# MegaSineShield.net
KiCad netlist of a schematic drawn in EAGLE
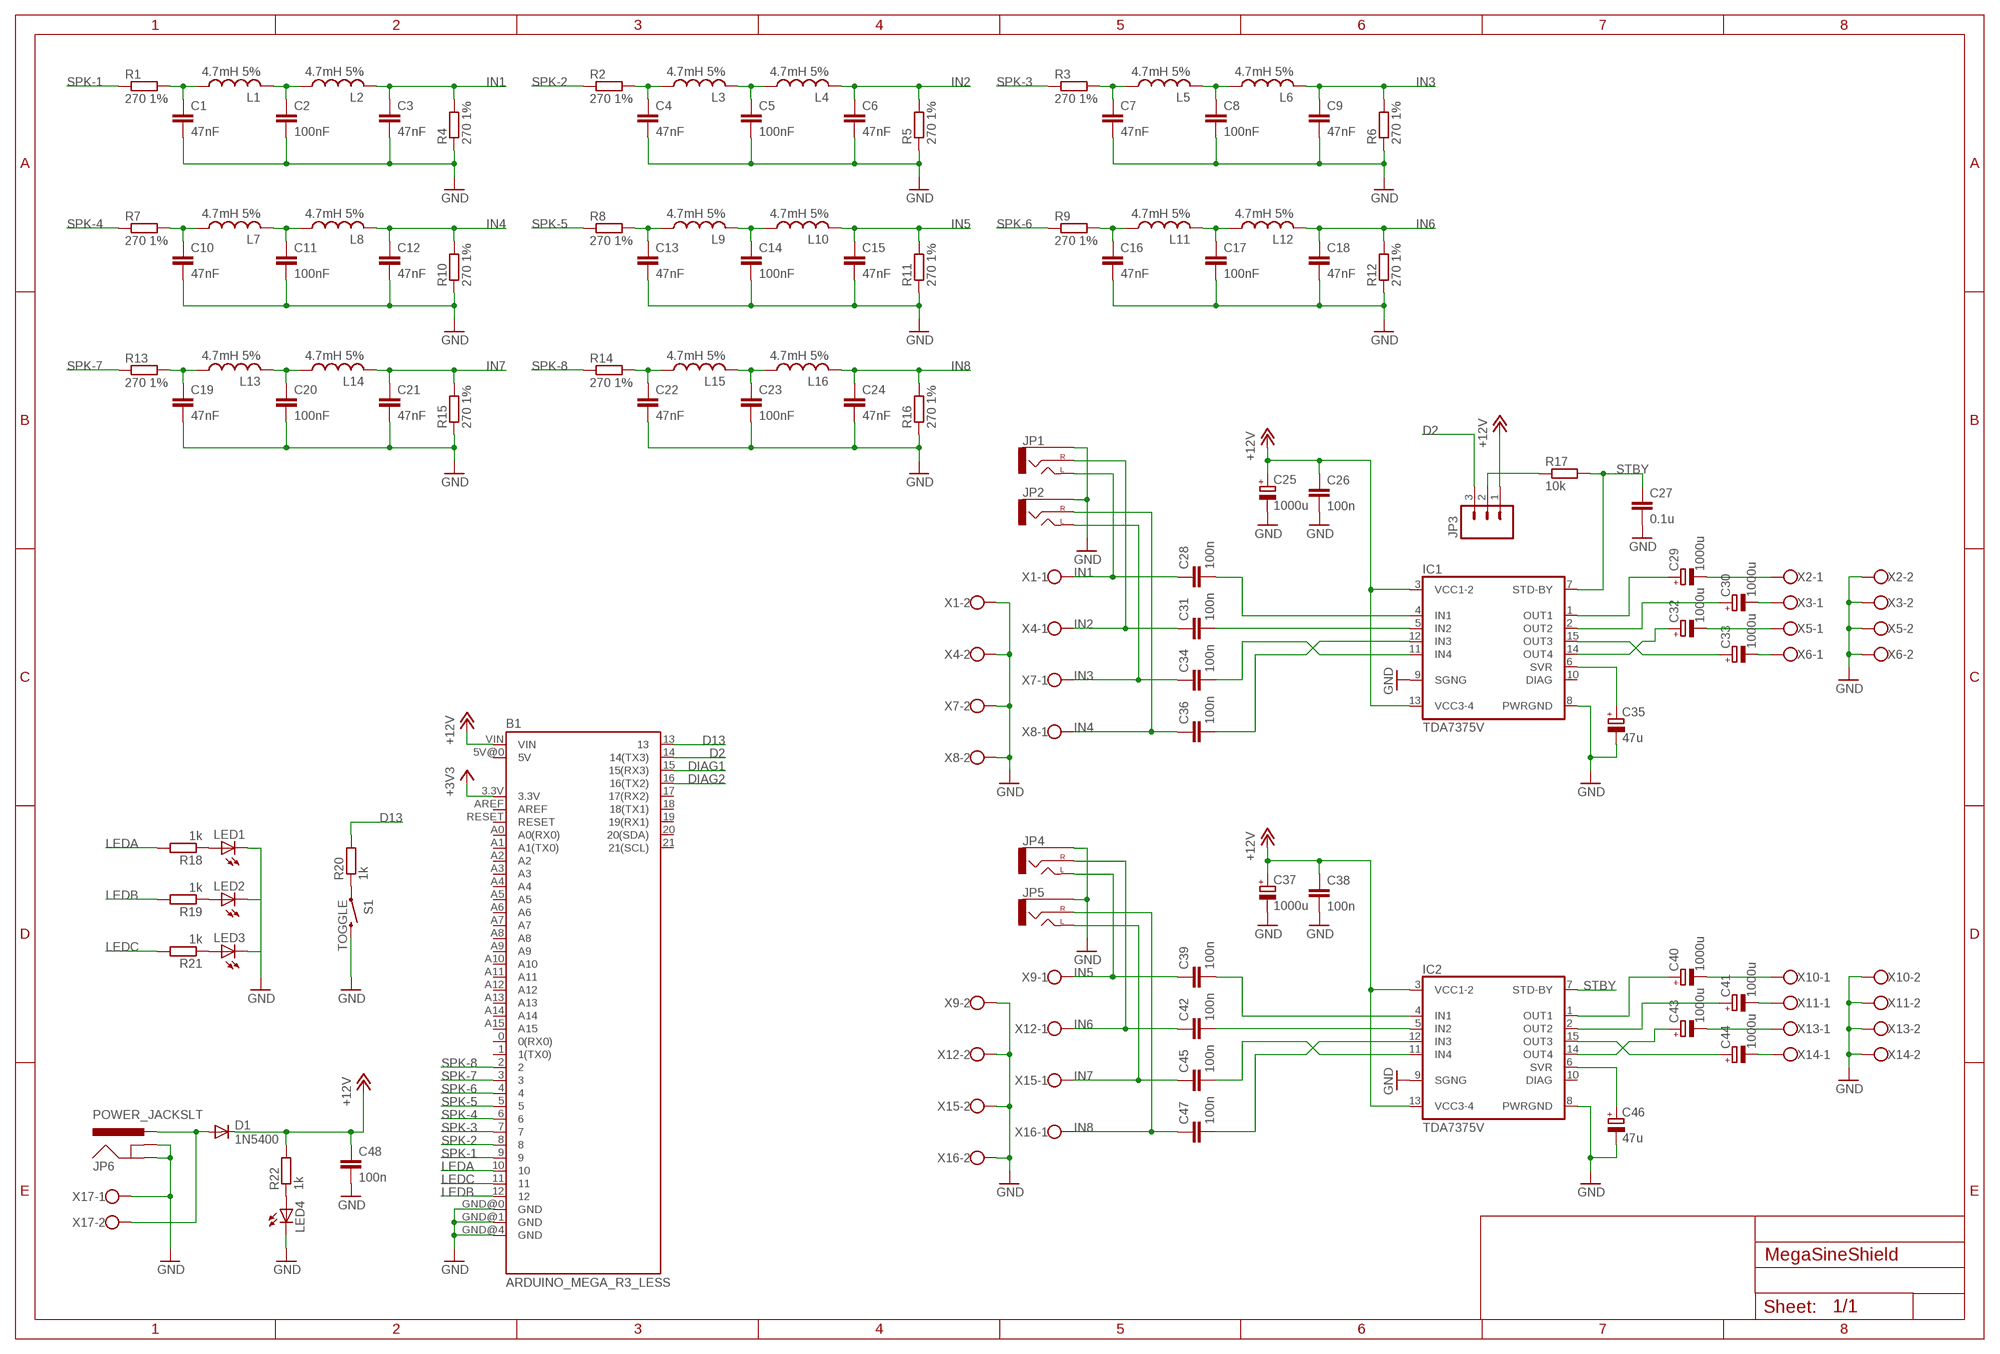
[diagram p0: schematic, sheet 1]

(export (version "E")
  (design (tool "Eeschema 10.0.6"))
  (components
    (comp (ref "B1")
      (value "ARDUINO_MEGA_R3_LESS")
      (footprint "eagle-import:ARDUINO_MEGA_LESS")
      (libsource (lib "eagle-import") (part "ARDUINO_MEGA_R3_LESS"))
    )
    (comp (ref "C1")
      (value "47nF")
      (footprint "eagle-import:C025-025X050")
      (libsource (lib "eagle-import") (part "C-EU025-025X050"))
    )
    (comp (ref "C2")
      (value "100nF")
      (footprint "eagle-import:C025-025X050")
      (libsource (lib "eagle-import") (part "C-EU025-025X050"))
    )
    (comp (ref "C3")
      (value "47nF")
      (footprint "eagle-import:C025-025X050")
      (libsource (lib "eagle-import") (part "C-EU025-025X050"))
    )
    (comp (ref "C4")
      (value "47nF")
      (footprint "eagle-import:C025-025X050")
      (libsource (lib "eagle-import") (part "C-EU025-025X050"))
    )
    (comp (ref "C5")
      (value "100nF")
      (footprint "eagle-import:C025-025X050")
      (libsource (lib "eagle-import") (part "C-EU025-025X050"))
    )
    (comp (ref "C6")
      (value "47nF")
      (footprint "eagle-import:C025-025X050")
      (libsource (lib "eagle-import") (part "C-EU025-025X050"))
    )
    (comp (ref "C7")
      (value "47nF")
      (footprint "eagle-import:C025-025X050")
      (libsource (lib "eagle-import") (part "C-EU025-025X050"))
    )
    (comp (ref "C8")
      (value "100nF")
      (footprint "eagle-import:C025-025X050")
      (libsource (lib "eagle-import") (part "C-EU025-025X050"))
    )
    (comp (ref "C9")
      (value "47nF")
      (footprint "eagle-import:C025-025X050")
      (libsource (lib "eagle-import") (part "C-EU025-025X050"))
    )
    (comp (ref "C10")
      (value "47nF")
      (footprint "eagle-import:C025-025X050")
      (libsource (lib "eagle-import") (part "C-EU025-025X050"))
    )
    (comp (ref "C11")
      (value "100nF")
      (footprint "eagle-import:C025-025X050")
      (libsource (lib "eagle-import") (part "C-EU025-025X050"))
    )
    (comp (ref "C12")
      (value "47nF")
      (footprint "eagle-import:C025-025X050")
      (libsource (lib "eagle-import") (part "C-EU025-025X050"))
    )
    (comp (ref "C13")
      (value "47nF")
      (footprint "eagle-import:C025-025X050")
      (libsource (lib "eagle-import") (part "C-EU025-025X050"))
    )
    (comp (ref "C14")
      (value "100nF")
      (footprint "eagle-import:C025-025X050")
      (libsource (lib "eagle-import") (part "C-EU025-025X050"))
    )
    (comp (ref "C15")
      (value "47nF")
      (footprint "eagle-import:C025-025X050")
      (libsource (lib "eagle-import") (part "C-EU025-025X050"))
    )
    (comp (ref "C16")
      (value "47nF")
      (footprint "eagle-import:C025-025X050")
      (libsource (lib "eagle-import") (part "C-EU025-025X050"))
    )
    (comp (ref "C17")
      (value "100nF")
      (footprint "eagle-import:C025-025X050")
      (libsource (lib "eagle-import") (part "C-EU025-025X050"))
    )
    (comp (ref "C18")
      (value "47nF")
      (footprint "eagle-import:C025-025X050")
      (libsource (lib "eagle-import") (part "C-EU025-025X050"))
    )
    (comp (ref "C19")
      (value "47nF")
      (footprint "eagle-import:C025-025X050")
      (libsource (lib "eagle-import") (part "C-EU025-025X050"))
    )
    (comp (ref "C20")
      (value "100nF")
      (footprint "eagle-import:C025-025X050")
      (libsource (lib "eagle-import") (part "C-EU025-025X050"))
    )
    (comp (ref "C21")
      (value "47nF")
      (footprint "eagle-import:C025-025X050")
      (libsource (lib "eagle-import") (part "C-EU025-025X050"))
    )
    (comp (ref "C22")
      (value "47nF")
      (footprint "eagle-import:C025-025X050")
      (libsource (lib "eagle-import") (part "C-EU025-025X050"))
    )
    (comp (ref "C23")
      (value "100nF")
      (footprint "eagle-import:C025-025X050")
      (libsource (lib "eagle-import") (part "C-EU025-025X050"))
    )
    (comp (ref "C24")
      (value "47nF")
      (footprint "eagle-import:C025-025X050")
      (libsource (lib "eagle-import") (part "C-EU025-025X050"))
    )
    (comp (ref "C25")
      (value "1000u")
      (footprint "eagle-import:E5-10,5")
      (libsource (lib "eagle-import") (part "CPOL-EUE5-10.5"))
    )
    (comp (ref "C26")
      (value "100n")
      (footprint "eagle-import:C025-025X050")
      (libsource (lib "eagle-import") (part "C-EU025-025X050"))
    )
    (comp (ref "C27")
      (value "0.1u")
      (footprint "eagle-import:C025-025X050")
      (libsource (lib "eagle-import") (part "C-EU025-025X050"))
    )
    (comp (ref "C28")
      (value "100n")
      (footprint "eagle-import:C025-025X050")
      (libsource (lib "eagle-import") (part "C-EU025-025X050"))
    )
    (comp (ref "C29")
      (value "1000u")
      (footprint "eagle-import:E5-10,5")
      (libsource (lib "eagle-import") (part "CPOL-EUE5-10.5"))
    )
    (comp (ref "C30")
      (value "1000u")
      (footprint "eagle-import:E5-10,5")
      (libsource (lib "eagle-import") (part "CPOL-EUE5-10.5"))
    )
    (comp (ref "C31")
      (value "100n")
      (footprint "eagle-import:C025-025X050")
      (libsource (lib "eagle-import") (part "C-EU025-025X050"))
    )
    (comp (ref "C32")
      (value "1000u")
      (footprint "eagle-import:E5-10,5")
      (libsource (lib "eagle-import") (part "CPOL-EUE5-10.5"))
    )
    (comp (ref "C33")
      (value "1000u")
      (footprint "eagle-import:E5-10,5")
      (libsource (lib "eagle-import") (part "CPOL-EUE5-10.5"))
    )
    (comp (ref "C34")
      (value "100n")
      (footprint "eagle-import:C025-025X050")
      (libsource (lib "eagle-import") (part "C-EU025-025X050"))
    )
    (comp (ref "C35")
      (value "47u")
      (footprint "eagle-import:E2,5-5")
      (libsource (lib "eagle-import") (part "CPOL-EUE2.5-5"))
    )
    (comp (ref "C36")
      (value "100n")
      (footprint "eagle-import:C025-025X050")
      (libsource (lib "eagle-import") (part "C-EU025-025X050"))
    )
    (comp (ref "C37")
      (value "1000u")
      (footprint "eagle-import:E5-10,5")
      (libsource (lib "eagle-import") (part "CPOL-EUE5-10.5"))
    )
    (comp (ref "C38")
      (value "100n")
      (footprint "eagle-import:C025-025X050")
      (libsource (lib "eagle-import") (part "C-EU025-025X050"))
    )
    (comp (ref "C39")
      (value "100n")
      (footprint "eagle-import:C025-025X050")
      (libsource (lib "eagle-import") (part "C-EU025-025X050"))
    )
    (comp (ref "C40")
      (value "1000u")
      (footprint "eagle-import:E5-10,5")
      (libsource (lib "eagle-import") (part "CPOL-EUE5-10.5"))
    )
    (comp (ref "C41")
      (value "1000u")
      (footprint "eagle-import:E5-10,5")
      (libsource (lib "eagle-import") (part "CPOL-EUE5-10.5"))
    )
    (comp (ref "C42")
      (value "100n")
      (footprint "eagle-import:C025-025X050")
      (libsource (lib "eagle-import") (part "C-EU025-025X050"))
    )
    (comp (ref "C43")
      (value "1000u")
      (footprint "eagle-import:E5-10,5")
      (libsource (lib "eagle-import") (part "CPOL-EUE5-10.5"))
    )
    (comp (ref "C44")
      (value "1000u")
      (footprint "eagle-import:E5-10,5")
      (libsource (lib "eagle-import") (part "CPOL-EUE5-10.5"))
    )
    (comp (ref "C45")
      (value "100n")
      (footprint "eagle-import:C025-025X050")
      (libsource (lib "eagle-import") (part "C-EU025-025X050"))
    )
    (comp (ref "C46")
      (value "47u")
      (footprint "eagle-import:E2,5-5")
      (libsource (lib "eagle-import") (part "CPOL-EUE2.5-5"))
    )
    (comp (ref "C47")
      (value "100n")
      (footprint "eagle-import:C025-025X050")
      (libsource (lib "eagle-import") (part "C-EU025-025X050"))
    )
    (comp (ref "C48")
      (value "100n")
      (footprint "eagle-import:C025-025X050")
      (libsource (lib "eagle-import") (part "C-EU025-025X050"))
    )
    (comp (ref "D1")
      (value "1N5400")
      (footprint "eagle-import:DO201-15")
      (libsource (lib "eagle-import") (part "1N5400"))
    )
    (comp (ref "IC1")
      (value "TDA7375V")
      (footprint "eagle-import:MULTIWATT-15V")
      (libsource (lib "eagle-import") (part "TDA7375V"))
    )
    (comp (ref "IC2")
      (value "TDA7375V")
      (footprint "eagle-import:MULTIWATT-15V")
      (libsource (lib "eagle-import") (part "TDA7375V"))
    )
    (comp (ref "JP1")
      (value "AUDIO-JACKPTH")
      (footprint "eagle-import:AUDIO-JACK")
      (libsource (lib "eagle-import") (part "AUDIO-JACKPTH"))
    )
    (comp (ref "JP2")
      (value "AUDIO-JACKPTH")
      (footprint "eagle-import:AUDIO-JACK")
      (libsource (lib "eagle-import") (part "AUDIO-JACKPTH"))
    )
    (comp (ref "JP3")
      (value "M03LOCK")
      (footprint "eagle-import:1X03_LOCK")
      (libsource (lib "eagle-import") (part "M03LOCK"))
    )
    (comp (ref "JP4")
      (value "AUDIO-JACKPTH")
      (footprint "eagle-import:AUDIO-JACK")
      (libsource (lib "eagle-import") (part "AUDIO-JACKPTH"))
    )
    (comp (ref "JP5")
      (value "AUDIO-JACKPTH")
      (footprint "eagle-import:AUDIO-JACK")
      (libsource (lib "eagle-import") (part "AUDIO-JACKPTH"))
    )
    (comp (ref "JP6")
      (value "POWER_JACKSLT")
      (footprint "eagle-import:POWER_JACK_SLOT")
      (libsource (lib "eagle-import") (part "POWER_JACKSLT"))
    )
    (comp (ref "L1")
      (value "4.7mH 5%")
      (footprint "eagle-import:0207_2V")
      (libsource (lib "eagle-import") (part "L-US0207/2V"))
    )
    (comp (ref "L2")
      (value "4.7mH 5%")
      (footprint "eagle-import:0207_2V")
      (libsource (lib "eagle-import") (part "L-US0207/2V"))
    )
    (comp (ref "L3")
      (value "4.7mH 5%")
      (footprint "eagle-import:0207_2V")
      (libsource (lib "eagle-import") (part "L-US0207/2V"))
    )
    (comp (ref "L4")
      (value "4.7mH 5%")
      (footprint "eagle-import:0207_2V")
      (libsource (lib "eagle-import") (part "L-US0207/2V"))
    )
    (comp (ref "L5")
      (value "4.7mH 5%")
      (footprint "eagle-import:0207_2V")
      (libsource (lib "eagle-import") (part "L-US0207/2V"))
    )
    (comp (ref "L6")
      (value "4.7mH 5%")
      (footprint "eagle-import:0207_2V")
      (libsource (lib "eagle-import") (part "L-US0207/2V"))
    )
    (comp (ref "L7")
      (value "4.7mH 5%")
      (footprint "eagle-import:0207_2V")
      (libsource (lib "eagle-import") (part "L-US0207/2V"))
    )
    (comp (ref "L8")
      (value "4.7mH 5%")
      (footprint "eagle-import:0207_2V")
      (libsource (lib "eagle-import") (part "L-US0207/2V"))
    )
    (comp (ref "L9")
      (value "4.7mH 5%")
      (footprint "eagle-import:0207_2V")
      (libsource (lib "eagle-import") (part "L-US0207/2V"))
    )
    (comp (ref "L10")
      (value "4.7mH 5%")
      (footprint "eagle-import:0207_2V")
      (libsource (lib "eagle-import") (part "L-US0207/2V"))
    )
    (comp (ref "L11")
      (value "4.7mH 5%")
      (footprint "eagle-import:0207_2V")
      (libsource (lib "eagle-import") (part "L-US0207/2V"))
    )
    (comp (ref "L12")
      (value "4.7mH 5%")
      (footprint "eagle-import:0207_2V")
      (libsource (lib "eagle-import") (part "L-US0207/2V"))
    )
    (comp (ref "L13")
      (value "4.7mH 5%")
      (footprint "eagle-import:0207_2V")
      (libsource (lib "eagle-import") (part "L-US0207/2V"))
    )
    (comp (ref "L14")
      (value "4.7mH 5%")
      (footprint "eagle-import:0207_2V")
      (libsource (lib "eagle-import") (part "L-US0207/2V"))
    )
    (comp (ref "L15")
      (value "4.7mH 5%")
      (footprint "eagle-import:0207_2V")
      (libsource (lib "eagle-import") (part "L-US0207/2V"))
    )
    (comp (ref "L16")
      (value "4.7mH 5%")
      (footprint "eagle-import:0207_2V")
      (libsource (lib "eagle-import") (part "L-US0207/2V"))
    )
    (comp (ref "LED1")
      (value "LED5MM")
      (footprint "eagle-import:LED5MM")
      (libsource (lib "eagle-import") (part "LED5MM"))
    )
    (comp (ref "LED2")
      (value "LED5MM")
      (footprint "eagle-import:LED5MM")
      (libsource (lib "eagle-import") (part "LED5MM"))
    )
    (comp (ref "LED3")
      (value "LED5MM")
      (footprint "eagle-import:LED5MM")
      (libsource (lib "eagle-import") (part "LED5MM"))
    )
    (comp (ref "LED4")
      (value "LED5MM")
      (footprint "eagle-import:LED5MM")
      (libsource (lib "eagle-import") (part "LED5MM"))
    )
    (comp (ref "R1")
      (value "270 1%")
      (footprint "eagle-import:0207_2V")
      (libsource (lib "eagle-import") (part "R-EU_0207/2V"))
    )
    (comp (ref "R2")
      (value "270 1%")
      (footprint "eagle-import:0207_2V")
      (libsource (lib "eagle-import") (part "R-EU_0207/2V"))
    )
    (comp (ref "R3")
      (value "270 1%")
      (footprint "eagle-import:0207_2V")
      (libsource (lib "eagle-import") (part "R-EU_0207/2V"))
    )
    (comp (ref "R4")
      (value "270 1%")
      (footprint "eagle-import:0207_2V")
      (libsource (lib "eagle-import") (part "R-EU_0207/2V"))
    )
    (comp (ref "R5")
      (value "270 1%")
      (footprint "eagle-import:0207_2V")
      (libsource (lib "eagle-import") (part "R-EU_0207/2V"))
    )
    (comp (ref "R6")
      (value "270 1%")
      (footprint "eagle-import:0207_2V")
      (libsource (lib "eagle-import") (part "R-EU_0207/2V"))
    )
    (comp (ref "R7")
      (value "270 1%")
      (footprint "eagle-import:0207_2V")
      (libsource (lib "eagle-import") (part "R-EU_0207/2V"))
    )
    (comp (ref "R8")
      (value "270 1%")
      (footprint "eagle-import:0207_2V")
      (libsource (lib "eagle-import") (part "R-EU_0207/2V"))
    )
    (comp (ref "R9")
      (value "270 1%")
      (footprint "eagle-import:0207_2V")
      (libsource (lib "eagle-import") (part "R-EU_0207/2V"))
    )
    (comp (ref "R10")
      (value "270 1%")
      (footprint "eagle-import:0207_2V")
      (libsource (lib "eagle-import") (part "R-EU_0207/2V"))
    )
    (comp (ref "R11")
      (value "270 1%")
      (footprint "eagle-import:0207_2V")
      (libsource (lib "eagle-import") (part "R-EU_0207/2V"))
    )
    (comp (ref "R12")
      (value "270 1%")
      (footprint "eagle-import:0207_2V")
      (libsource (lib "eagle-import") (part "R-EU_0207/2V"))
    )
    (comp (ref "R13")
      (value "270 1%")
      (footprint "eagle-import:0207_2V")
      (libsource (lib "eagle-import") (part "R-EU_0207/2V"))
    )
    (comp (ref "R14")
      (value "270 1%")
      (footprint "eagle-import:0207_2V")
      (libsource (lib "eagle-import") (part "R-EU_0207/2V"))
    )
    (comp (ref "R15")
      (value "270 1%")
      (footprint "eagle-import:0207_2V")
      (libsource (lib "eagle-import") (part "R-EU_0207/2V"))
    )
    (comp (ref "R16")
      (value "270 1%")
      (footprint "eagle-import:0207_2V")
      (libsource (lib "eagle-import") (part "R-EU_0207/2V"))
    )
    (comp (ref "R17")
      (value "10k")
      (footprint "eagle-import:0207_2V")
      (libsource (lib "eagle-import") (part "R-EU_0207/2V"))
    )
    (comp (ref "R18")
      (value "1k")
      (footprint "eagle-import:0207_2V")
      (libsource (lib "eagle-import") (part "R-EU_0207/2V"))
    )
    (comp (ref "R19")
      (value "1k")
      (footprint "eagle-import:0207_2V")
      (libsource (lib "eagle-import") (part "R-EU_0207/2V"))
    )
    (comp (ref "R20")
      (value "1k")
      (footprint "eagle-import:0207_2V")
      (libsource (lib "eagle-import") (part "R-EU_0207/2V"))
    )
    (comp (ref "R21")
      (value "1k")
      (footprint "eagle-import:0207_2V")
      (libsource (lib "eagle-import") (part "R-EU_0207/2V"))
    )
    (comp (ref "R22")
      (value "1k")
      (footprint "eagle-import:0207_2V")
      (libsource (lib "eagle-import") (part "R-EU_0207/2V"))
    )
    (comp (ref "S1")
      (value "TOGGLE")
      (footprint "eagle-import:TACTILE-PTH")
      (libsource (lib "eagle-import") (part "SWITCH-MOMENTARY-2PTH"))
    )
    (comp (ref "X1")
      (value "W237-102")
      (footprint "eagle-import:W237-102")
      (fields (field (name "MPN") "237-102"))
      (libsource (lib "eagle-import") (part "W237-102"))
    )
    (comp (ref "X2")
      (value "W237-102")
      (footprint "eagle-import:W237-102")
      (fields (field (name "MPN") "237-102"))
      (libsource (lib "eagle-import") (part "W237-102"))
    )
    (comp (ref "X3")
      (value "W237-102")
      (footprint "eagle-import:W237-102")
      (fields (field (name "MPN") "237-102"))
      (libsource (lib "eagle-import") (part "W237-102"))
    )
    (comp (ref "X4")
      (value "W237-102")
      (footprint "eagle-import:W237-102")
      (fields (field (name "MPN") "237-102"))
      (libsource (lib "eagle-import") (part "W237-102"))
    )
    (comp (ref "X5")
      (value "W237-102")
      (footprint "eagle-import:W237-102")
      (fields (field (name "MPN") "237-102"))
      (libsource (lib "eagle-import") (part "W237-102"))
    )
    (comp (ref "X6")
      (value "W237-102")
      (footprint "eagle-import:W237-102")
      (fields (field (name "MPN") "237-102"))
      (libsource (lib "eagle-import") (part "W237-102"))
    )
    (comp (ref "X7")
      (value "W237-102")
      (footprint "eagle-import:W237-102")
      (fields (field (name "MPN") "237-102"))
      (libsource (lib "eagle-import") (part "W237-102"))
    )
    (comp (ref "X8")
      (value "W237-102")
      (footprint "eagle-import:W237-102")
      (fields (field (name "MPN") "237-102"))
      (libsource (lib "eagle-import") (part "W237-102"))
    )
    (comp (ref "X9")
      (value "W237-102")
      (footprint "eagle-import:W237-102")
      (fields (field (name "MPN") "237-102"))
      (libsource (lib "eagle-import") (part "W237-102"))
    )
    (comp (ref "X10")
      (value "W237-102")
      (footprint "eagle-import:W237-102")
      (fields (field (name "MPN") "237-102"))
      (libsource (lib "eagle-import") (part "W237-102"))
    )
    (comp (ref "X11")
      (value "W237-102")
      (footprint "eagle-import:W237-102")
      (fields (field (name "MPN") "237-102"))
      (libsource (lib "eagle-import") (part "W237-102"))
    )
    (comp (ref "X12")
      (value "W237-102")
      (footprint "eagle-import:W237-102")
      (fields (field (name "MPN") "237-102"))
      (libsource (lib "eagle-import") (part "W237-102"))
    )
    (comp (ref "X13")
      (value "W237-102")
      (footprint "eagle-import:W237-102")
      (fields (field (name "MPN") "237-102"))
      (libsource (lib "eagle-import") (part "W237-102"))
    )
    (comp (ref "X14")
      (value "W237-102")
      (footprint "eagle-import:W237-102")
      (fields (field (name "MPN") "237-102"))
      (libsource (lib "eagle-import") (part "W237-102"))
    )
    (comp (ref "X15")
      (value "W237-102")
      (footprint "eagle-import:W237-102")
      (fields (field (name "MPN") "237-102"))
      (libsource (lib "eagle-import") (part "W237-102"))
    )
    (comp (ref "X16")
      (value "W237-102")
      (footprint "eagle-import:W237-102")
      (fields (field (name "MPN") "237-102"))
      (libsource (lib "eagle-import") (part "W237-102"))
    )
    (comp (ref "X17")
      (value "W237-102")
      (footprint "eagle-import:W237-102")
      (fields (field (name "MPN") "237-102"))
      (libsource (lib "eagle-import") (part "W237-102"))
    )
  )
  (nets
    (net (code "1") (name "+3V3") (class "Default")
      (node (ref "B1") (pin "3.3V") (pinfunction "3.3V_3.3V") (pintype "bidirectional"))
    )
    (net (code "2") (name "+12V") (class "Default")
      (node (ref "B1") (pin "VIN") (pinfunction "VIN_VIN") (pintype "bidirectional"))
      (node (ref "C25") (pin "+") (pinfunction "+_+") (pintype "passive"))
      (node (ref "C26") (pin "1") (pinfunction "1_1") (pintype "passive"))
      (node (ref "C37") (pin "+") (pinfunction "+_+") (pintype "passive"))
      (node (ref "C38") (pin "1") (pinfunction "1_1") (pintype "passive"))
      (node (ref "C48") (pin "1") (pinfunction "1_1") (pintype "passive"))
      (node (ref "D1") (pin "C") (pinfunction "C_C") (pintype "passive"))
      (node (ref "IC1") (pin "13") (pinfunction "VCC3-4_13") (pintype "power_in"))
      (node (ref "IC1") (pin "3") (pinfunction "VCC1-2_3") (pintype "power_in"))
      (node (ref "IC2") (pin "13") (pinfunction "VCC3-4_13") (pintype "power_in"))
      (node (ref "IC2") (pin "3") (pinfunction "VCC1-2_3") (pintype "power_in"))
      (node (ref "JP3") (pin "1") (pinfunction "1_1") (pintype "passive"))
      (node (ref "R22") (pin "2") (pinfunction "2_2") (pintype "passive"))
    )
    (net (code "3") (name "/D2") (class "Default")
      (node (ref "B1") (pin "14") (pinfunction "14(TX3)_14") (pintype "bidirectional"))
      (node (ref "JP3") (pin "3") (pinfunction "3_3") (pintype "passive"))
    )
    (net (code "4") (name "/D13") (class "Default")
      (node (ref "B1") (pin "13") (pinfunction "13_13") (pintype "bidirectional"))
      (node (ref "R20") (pin "2") (pinfunction "2_2") (pintype "passive"))
    )
    (net (code "5") (name "/DIAG1") (class "Default")
      (node (ref "B1") (pin "15") (pinfunction "15(RX3)_15") (pintype "bidirectional"))
    )
    (net (code "6") (name "/DIAG2") (class "Default")
      (node (ref "B1") (pin "16") (pinfunction "16(TX2)_16") (pintype "bidirectional"))
    )
    (net (code "7") (name "/IN1") (class "Default")
      (node (ref "C28") (pin "1") (pinfunction "1_1") (pintype "passive"))
      (node (ref "C3") (pin "1") (pinfunction "1_1") (pintype "passive"))
      (node (ref "JP1") (pin "TIP") (pinfunction "LEFT_TIP") (pintype "bidirectional"))
      (node (ref "L2") (pin "2") (pinfunction "2_2") (pintype "passive"))
      (node (ref "R4") (pin "2") (pinfunction "2_2") (pintype "passive"))
      (node (ref "X1") (pin "1") (pinfunction "KL_1") (pintype "passive"))
    )
    (net (code "8") (name "/IN2") (class "Default")
      (node (ref "C31") (pin "1") (pinfunction "1_1") (pintype "passive"))
      (node (ref "C6") (pin "1") (pinfunction "1_1") (pintype "passive"))
      (node (ref "JP1") (pin "RING") (pinfunction "RIGHT_RING") (pintype "bidirectional"))
      (node (ref "L4") (pin "2") (pinfunction "2_2") (pintype "passive"))
      (node (ref "R5") (pin "2") (pinfunction "2_2") (pintype "passive"))
      (node (ref "X4") (pin "1") (pinfunction "KL_1") (pintype "passive"))
    )
    (net (code "9") (name "/IN3") (class "Default")
      (node (ref "C34") (pin "1") (pinfunction "1_1") (pintype "passive"))
      (node (ref "C9") (pin "1") (pinfunction "1_1") (pintype "passive"))
      (node (ref "JP2") (pin "TIP") (pinfunction "LEFT_TIP") (pintype "bidirectional"))
      (node (ref "L6") (pin "2") (pinfunction "2_2") (pintype "passive"))
      (node (ref "R6") (pin "2") (pinfunction "2_2") (pintype "passive"))
      (node (ref "X7") (pin "1") (pinfunction "KL_1") (pintype "passive"))
    )
    (net (code "10") (name "/IN4") (class "Default")
      (node (ref "C12") (pin "1") (pinfunction "1_1") (pintype "passive"))
      (node (ref "C36") (pin "1") (pinfunction "1_1") (pintype "passive"))
      (node (ref "JP2") (pin "RING") (pinfunction "RIGHT_RING") (pintype "bidirectional"))
      (node (ref "L8") (pin "2") (pinfunction "2_2") (pintype "passive"))
      (node (ref "R10") (pin "2") (pinfunction "2_2") (pintype "passive"))
      (node (ref "X8") (pin "1") (pinfunction "KL_1") (pintype "passive"))
    )
    (net (code "11") (name "/IN5") (class "Default")
      (node (ref "C15") (pin "1") (pinfunction "1_1") (pintype "passive"))
      (node (ref "C39") (pin "1") (pinfunction "1_1") (pintype "passive"))
      (node (ref "JP4") (pin "TIP") (pinfunction "LEFT_TIP") (pintype "bidirectional"))
      (node (ref "L10") (pin "2") (pinfunction "2_2") (pintype "passive"))
      (node (ref "R11") (pin "2") (pinfunction "2_2") (pintype "passive"))
      (node (ref "X9") (pin "1") (pinfunction "KL_1") (pintype "passive"))
    )
    (net (code "12") (name "/IN6") (class "Default")
      (node (ref "C18") (pin "1") (pinfunction "1_1") (pintype "passive"))
      (node (ref "C42") (pin "1") (pinfunction "1_1") (pintype "passive"))
      (node (ref "JP4") (pin "RING") (pinfunction "RIGHT_RING") (pintype "bidirectional"))
      (node (ref "L12") (pin "2") (pinfunction "2_2") (pintype "passive"))
      (node (ref "R12") (pin "2") (pinfunction "2_2") (pintype "passive"))
      (node (ref "X12") (pin "1") (pinfunction "KL_1") (pintype "passive"))
    )
    (net (code "13") (name "/IN7") (class "Default")
      (node (ref "C21") (pin "1") (pinfunction "1_1") (pintype "passive"))
      (node (ref "C45") (pin "1") (pinfunction "1_1") (pintype "passive"))
      (node (ref "JP5") (pin "TIP") (pinfunction "LEFT_TIP") (pintype "bidirectional"))
      (node (ref "L14") (pin "2") (pinfunction "2_2") (pintype "passive"))
      (node (ref "R15") (pin "2") (pinfunction "2_2") (pintype "passive"))
      (node (ref "X15") (pin "1") (pinfunction "KL_1") (pintype "passive"))
    )
    (net (code "14") (name "/IN8") (class "Default")
      (node (ref "C24") (pin "1") (pinfunction "1_1") (pintype "passive"))
      (node (ref "C47") (pin "1") (pinfunction "1_1") (pintype "passive"))
      (node (ref "JP5") (pin "RING") (pinfunction "RIGHT_RING") (pintype "bidirectional"))
      (node (ref "L16") (pin "2") (pinfunction "2_2") (pintype "passive"))
      (node (ref "R16") (pin "2") (pinfunction "2_2") (pintype "passive"))
      (node (ref "X16") (pin "1") (pinfunction "KL_1") (pintype "passive"))
    )
    (net (code "15") (name "/LEDA") (class "Default")
      (node (ref "B1") (pin "10") (pinfunction "10_10") (pintype "bidirectional"))
      (node (ref "R18") (pin "2") (pinfunction "2_2") (pintype "passive"))
    )
    (net (code "16") (name "/LEDB") (class "Default")
      (node (ref "B1") (pin "12") (pinfunction "12_12") (pintype "bidirectional"))
      (node (ref "R19") (pin "2") (pinfunction "2_2") (pintype "passive"))
    )
    (net (code "17") (name "/LEDC") (class "Default")
      (node (ref "B1") (pin "11") (pinfunction "11_11") (pintype "bidirectional"))
      (node (ref "R21") (pin "2") (pinfunction "2_2") (pintype "passive"))
    )
    (net (code "18") (name "/SPK-1") (class "Default")
      (node (ref "B1") (pin "9") (pinfunction "9_9") (pintype "bidirectional"))
      (node (ref "R1") (pin "1") (pinfunction "1_1") (pintype "passive"))
    )
    (net (code "19") (name "/SPK-2") (class "Default")
      (node (ref "B1") (pin "8") (pinfunction "8_8") (pintype "bidirectional"))
      (node (ref "R2") (pin "1") (pinfunction "1_1") (pintype "passive"))
    )
    (net (code "20") (name "/SPK-3") (class "Default")
      (node (ref "B1") (pin "7") (pinfunction "7_7") (pintype "bidirectional"))
      (node (ref "R3") (pin "1") (pinfunction "1_1") (pintype "passive"))
    )
    (net (code "21") (name "/SPK-4") (class "Default")
      (node (ref "B1") (pin "6") (pinfunction "6_6") (pintype "bidirectional"))
      (node (ref "R7") (pin "1") (pinfunction "1_1") (pintype "passive"))
    )
    (net (code "22") (name "/SPK-5") (class "Default")
      (node (ref "B1") (pin "5") (pinfunction "5_5") (pintype "bidirectional"))
      (node (ref "R8") (pin "1") (pinfunction "1_1") (pintype "passive"))
    )
    (net (code "23") (name "/SPK-6") (class "Default")
      (node (ref "B1") (pin "4") (pinfunction "4_4") (pintype "bidirectional"))
      (node (ref "R9") (pin "1") (pinfunction "1_1") (pintype "passive"))
    )
    (net (code "24") (name "/SPK-7") (class "Default")
      (node (ref "B1") (pin "3") (pinfunction "3_3") (pintype "bidirectional"))
      (node (ref "R13") (pin "1") (pinfunction "1_1") (pintype "passive"))
    )
    (net (code "25") (name "/SPK-8") (class "Default")
      (node (ref "B1") (pin "2") (pinfunction "2_2") (pintype "bidirectional"))
      (node (ref "R14") (pin "1") (pinfunction "1_1") (pintype "passive"))
    )
    (net (code "26") (name "/STBY") (class "Default")
      (node (ref "C27") (pin "1") (pinfunction "1_1") (pintype "passive"))
      (node (ref "IC1") (pin "7") (pinfunction "STD-BY_7") (pintype "input"))
      (node (ref "IC2") (pin "7") (pinfunction "STD-BY_7") (pintype "input"))
      (node (ref "R17") (pin "2") (pinfunction "2_2") (pintype "passive"))
    )
    (net (code "27") (name "GND") (class "Default")
      (node (ref "B1") (pin "GND@0") (pinfunction "GND_GND@0") (pintype "bidirectional"))
      (node (ref "B1") (pin "GND@1") (pinfunction "GND_GND@1") (pintype "bidirectional"))
      (node (ref "B1") (pin "GND@4") (pinfunction "GND_GND@4") (pintype "bidirectional"))
      (node (ref "C1") (pin "2") (pinfunction "2_2") (pintype "passive"))
      (node (ref "C10") (pin "2") (pinfunction "2_2") (pintype "passive"))
      (node (ref "C11") (pin "2") (pinfunction "2_2") (pintype "passive"))
      (node (ref "C12") (pin "2") (pinfunction "2_2") (pintype "passive"))
      (node (ref "C13") (pin "2") (pinfunction "2_2") (pintype "passive"))
      (node (ref "C14") (pin "2") (pinfunction "2_2") (pintype "passive"))
      (node (ref "C15") (pin "2") (pinfunction "2_2") (pintype "passive"))
      (node (ref "C16") (pin "2") (pinfunction "2_2") (pintype "passive"))
      (node (ref "C17") (pin "2") (pinfunction "2_2") (pintype "passive"))
      (node (ref "C18") (pin "2") (pinfunction "2_2") (pintype "passive"))
      (node (ref "C19") (pin "2") (pinfunction "2_2") (pintype "passive"))
      (node (ref "C2") (pin "2") (pinfunction "2_2") (pintype "passive"))
      (node (ref "C20") (pin "2") (pinfunction "2_2") (pintype "passive"))
      (node (ref "C21") (pin "2") (pinfunction "2_2") (pintype "passive"))
      (node (ref "C22") (pin "2") (pinfunction "2_2") (pintype "passive"))
      (node (ref "C23") (pin "2") (pinfunction "2_2") (pintype "passive"))
      (node (ref "C24") (pin "2") (pinfunction "2_2") (pintype "passive"))
      (node (ref "C25") (pin "-") (pinfunction "-_-") (pintype "passive"))
      (node (ref "C26") (pin "2") (pinfunction "2_2") (pintype "passive"))
      (node (ref "C27") (pin "2") (pinfunction "2_2") (pintype "passive"))
      (node (ref "C3") (pin "2") (pinfunction "2_2") (pintype "passive"))
      (node (ref "C35") (pin "-") (pinfunction "-_-") (pintype "passive"))
      (node (ref "C37") (pin "-") (pinfunction "-_-") (pintype "passive"))
      (node (ref "C38") (pin "2") (pinfunction "2_2") (pintype "passive"))
      (node (ref "C4") (pin "2") (pinfunction "2_2") (pintype "passive"))
      (node (ref "C46") (pin "-") (pinfunction "-_-") (pintype "passive"))
      (node (ref "C48") (pin "2") (pinfunction "2_2") (pintype "passive"))
      (node (ref "C5") (pin "2") (pinfunction "2_2") (pintype "passive"))
      (node (ref "C6") (pin "2") (pinfunction "2_2") (pintype "passive"))
      (node (ref "C7") (pin "2") (pinfunction "2_2") (pintype "passive"))
      (node (ref "C8") (pin "2") (pinfunction "2_2") (pintype "passive"))
      (node (ref "C9") (pin "2") (pinfunction "2_2") (pintype "passive"))
      (node (ref "IC1") (pin "8") (pinfunction "PWRGND_8") (pintype "power_in"))
      (node (ref "IC1") (pin "9") (pinfunction "SGNG_9") (pintype "power_in"))
      (node (ref "IC2") (pin "8") (pinfunction "PWRGND_8") (pintype "power_in"))
      (node (ref "IC2") (pin "9") (pinfunction "SGNG_9") (pintype "power_in"))
      (node (ref "JP1") (pin "SLEEVE") (pinfunction "SLEEVE_SLEEVE") (pintype "bidirectional"))
      (node (ref "JP2") (pin "SLEEVE") (pinfunction "SLEEVE_SLEEVE") (pintype "bidirectional"))
      (node (ref "JP4") (pin "SLEEVE") (pinfunction "SLEEVE_SLEEVE") (pintype "bidirectional"))
      (node (ref "JP5") (pin "SLEEVE") (pinfunction "SLEEVE_SLEEVE") (pintype "bidirectional"))
      (node (ref "JP6") (pin "GND@1") (pinfunction "GNDBREAK_GND@1") (pintype "bidirectional"))
      (node (ref "JP6") (pin "GND@2") (pinfunction "GND_GND@2") (pintype "bidirectional"))
      (node (ref "LED1") (pin "K") (pinfunction "C_K") (pintype "passive"))
      (node (ref "LED2") (pin "K") (pinfunction "C_K") (pintype "passive"))
      (node (ref "LED3") (pin "K") (pinfunction "C_K") (pintype "passive"))
      (node (ref "LED4") (pin "K") (pinfunction "C_K") (pintype "passive"))
      (node (ref "R10") (pin "1") (pinfunction "1_1") (pintype "passive"))
      (node (ref "R11") (pin "1") (pinfunction "1_1") (pintype "passive"))
      (node (ref "R12") (pin "1") (pinfunction "1_1") (pintype "passive"))
      (node (ref "R15") (pin "1") (pinfunction "1_1") (pintype "passive"))
      (node (ref "R16") (pin "1") (pinfunction "1_1") (pintype "passive"))
      (node (ref "R4") (pin "1") (pinfunction "1_1") (pintype "passive"))
      (node (ref "R5") (pin "1") (pinfunction "1_1") (pintype "passive"))
      (node (ref "R6") (pin "1") (pinfunction "1_1") (pintype "passive"))
      (node (ref "S1") (pin "3") (pinfunction "2_3") (pintype "passive"))
      (node (ref "X1") (pin "2") (pinfunction "KL_2") (pintype "passive"))
      (node (ref "X10") (pin "2") (pinfunction "KL_2") (pintype "passive"))
      (node (ref "X11") (pin "2") (pinfunction "KL_2") (pintype "passive"))
      (node (ref "X12") (pin "2") (pinfunction "KL_2") (pintype "passive"))
      (node (ref "X13") (pin "2") (pinfunction "KL_2") (pintype "passive"))
      (node (ref "X14") (pin "2") (pinfunction "KL_2") (pintype "passive"))
      (node (ref "X15") (pin "2") (pinfunction "KL_2") (pintype "passive"))
      (node (ref "X16") (pin "2") (pinfunction "KL_2") (pintype "passive"))
      (node (ref "X17") (pin "1") (pinfunction "KL_1") (pintype "passive"))
      (node (ref "X2") (pin "2") (pinfunction "KL_2") (pintype "passive"))
      (node (ref "X3") (pin "2") (pinfunction "KL_2") (pintype "passive"))
      (node (ref "X4") (pin "2") (pinfunction "KL_2") (pintype "passive"))
      (node (ref "X5") (pin "2") (pinfunction "KL_2") (pintype "passive"))
      (node (ref "X6") (pin "2") (pinfunction "KL_2") (pintype "passive"))
      (node (ref "X7") (pin "2") (pinfunction "KL_2") (pintype "passive"))
      (node (ref "X8") (pin "2") (pinfunction "KL_2") (pintype "passive"))
      (node (ref "X9") (pin "2") (pinfunction "KL_2") (pintype "passive"))
    )
    (net (code "28") (name "Net-(C1-Pad1)") (class "Default")
      (node (ref "C1") (pin "1") (pinfunction "1_1") (pintype "passive"))
      (node (ref "L1") (pin "1") (pinfunction "1_1") (pintype "passive"))
      (node (ref "R1") (pin "2") (pinfunction "2_2") (pintype "passive"))
    )
    (net (code "29") (name "Net-(C2-Pad1)") (class "Default")
      (node (ref "C2") (pin "1") (pinfunction "1_1") (pintype "passive"))
      (node (ref "L1") (pin "2") (pinfunction "2_2") (pintype "passive"))
      (node (ref "L2") (pin "1") (pinfunction "1_1") (pintype "passive"))
    )
    (net (code "30") (name "Net-(C4-Pad1)") (class "Default")
      (node (ref "C4") (pin "1") (pinfunction "1_1") (pintype "passive"))
      (node (ref "L3") (pin "1") (pinfunction "1_1") (pintype "passive"))
      (node (ref "R2") (pin "2") (pinfunction "2_2") (pintype "passive"))
    )
    (net (code "31") (name "Net-(C5-Pad1)") (class "Default")
      (node (ref "C5") (pin "1") (pinfunction "1_1") (pintype "passive"))
      (node (ref "L3") (pin "2") (pinfunction "2_2") (pintype "passive"))
      (node (ref "L4") (pin "1") (pinfunction "1_1") (pintype "passive"))
    )
    (net (code "32") (name "Net-(C7-Pad1)") (class "Default")
      (node (ref "C7") (pin "1") (pinfunction "1_1") (pintype "passive"))
      (node (ref "L5") (pin "1") (pinfunction "1_1") (pintype "passive"))
      (node (ref "R3") (pin "2") (pinfunction "2_2") (pintype "passive"))
    )
    (net (code "33") (name "Net-(C8-Pad1)") (class "Default")
      (node (ref "C8") (pin "1") (pinfunction "1_1") (pintype "passive"))
      (node (ref "L5") (pin "2") (pinfunction "2_2") (pintype "passive"))
      (node (ref "L6") (pin "1") (pinfunction "1_1") (pintype "passive"))
    )
    (net (code "34") (name "Net-(C10-Pad1)") (class "Default")
      (node (ref "C10") (pin "1") (pinfunction "1_1") (pintype "passive"))
      (node (ref "L7") (pin "1") (pinfunction "1_1") (pintype "passive"))
      (node (ref "R7") (pin "2") (pinfunction "2_2") (pintype "passive"))
    )
    (net (code "35") (name "Net-(C11-Pad1)") (class "Default")
      (node (ref "C11") (pin "1") (pinfunction "1_1") (pintype "passive"))
      (node (ref "L7") (pin "2") (pinfunction "2_2") (pintype "passive"))
      (node (ref "L8") (pin "1") (pinfunction "1_1") (pintype "passive"))
    )
    (net (code "36") (name "Net-(C13-Pad1)") (class "Default")
      (node (ref "C13") (pin "1") (pinfunction "1_1") (pintype "passive"))
      (node (ref "L9") (pin "1") (pinfunction "1_1") (pintype "passive"))
      (node (ref "R8") (pin "2") (pinfunction "2_2") (pintype "passive"))
    )
    (net (code "37") (name "Net-(C14-Pad1)") (class "Default")
      (node (ref "C14") (pin "1") (pinfunction "1_1") (pintype "passive"))
      (node (ref "L10") (pin "1") (pinfunction "1_1") (pintype "passive"))
      (node (ref "L9") (pin "2") (pinfunction "2_2") (pintype "passive"))
    )
    (net (code "38") (name "Net-(C16-Pad1)") (class "Default")
      (node (ref "C16") (pin "1") (pinfunction "1_1") (pintype "passive"))
      (node (ref "L11") (pin "1") (pinfunction "1_1") (pintype "passive"))
      (node (ref "R9") (pin "2") (pinfunction "2_2") (pintype "passive"))
    )
    (net (code "39") (name "Net-(C17-Pad1)") (class "Default")
      (node (ref "C17") (pin "1") (pinfunction "1_1") (pintype "passive"))
      (node (ref "L11") (pin "2") (pinfunction "2_2") (pintype "passive"))
      (node (ref "L12") (pin "1") (pinfunction "1_1") (pintype "passive"))
    )
    (net (code "40") (name "Net-(C19-Pad1)") (class "Default")
      (node (ref "C19") (pin "1") (pinfunction "1_1") (pintype "passive"))
      (node (ref "L13") (pin "1") (pinfunction "1_1") (pintype "passive"))
      (node (ref "R13") (pin "2") (pinfunction "2_2") (pintype "passive"))
    )
    (net (code "41") (name "Net-(C20-Pad1)") (class "Default")
      (node (ref "C20") (pin "1") (pinfunction "1_1") (pintype "passive"))
      (node (ref "L13") (pin "2") (pinfunction "2_2") (pintype "passive"))
      (node (ref "L14") (pin "1") (pinfunction "1_1") (pintype "passive"))
    )
    (net (code "42") (name "Net-(C22-Pad1)") (class "Default")
      (node (ref "C22") (pin "1") (pinfunction "1_1") (pintype "passive"))
      (node (ref "L15") (pin "1") (pinfunction "1_1") (pintype "passive"))
      (node (ref "R14") (pin "2") (pinfunction "2_2") (pintype "passive"))
    )
    (net (code "43") (name "Net-(C23-Pad1)") (class "Default")
      (node (ref "C23") (pin "1") (pinfunction "1_1") (pintype "passive"))
      (node (ref "L15") (pin "2") (pinfunction "2_2") (pintype "passive"))
      (node (ref "L16") (pin "1") (pinfunction "1_1") (pintype "passive"))
    )
    (net (code "44") (name "Net-(IC1-IN1)") (class "Default")
      (node (ref "C28") (pin "2") (pinfunction "2_2") (pintype "passive"))
      (node (ref "IC1") (pin "4") (pinfunction "IN1_4") (pintype "input"))
    )
    (net (code "45") (name "Net-(IC1-IN2)") (class "Default")
      (node (ref "C31") (pin "2") (pinfunction "2_2") (pintype "passive"))
      (node (ref "IC1") (pin "5") (pinfunction "IN2_5") (pintype "input"))
    )
    (net (code "46") (name "Net-(IC1-IN3)") (class "Default")
      (node (ref "C36") (pin "2") (pinfunction "2_2") (pintype "passive"))
      (node (ref "IC1") (pin "12") (pinfunction "IN3_12") (pintype "input"))
    )
    (net (code "47") (name "Net-(IC1-IN4)") (class "Default")
      (node (ref "C34") (pin "2") (pinfunction "2_2") (pintype "passive"))
      (node (ref "IC1") (pin "11") (pinfunction "IN4_11") (pintype "input"))
    )
    (net (code "48") (name "Net-(IC1-OUT1)") (class "Default")
      (node (ref "C29") (pin "+") (pinfunction "+_+") (pintype "passive"))
      (node (ref "IC1") (pin "1") (pinfunction "OUT1_1") (pintype "output"))
    )
    (net (code "49") (name "Net-(IC1-OUT2)") (class "Default")
      (node (ref "C30") (pin "+") (pinfunction "+_+") (pintype "passive"))
      (node (ref "IC1") (pin "2") (pinfunction "OUT2_2") (pintype "output"))
    )
    (net (code "50") (name "Net-(IC1-OUT3)") (class "Default")
      (node (ref "C33") (pin "+") (pinfunction "+_+") (pintype "passive"))
      (node (ref "IC1") (pin "15") (pinfunction "OUT3_15") (pintype "output"))
    )
    (net (code "51") (name "Net-(IC1-OUT4)") (class "Default")
      (node (ref "C32") (pin "+") (pinfunction "+_+") (pintype "passive"))
      (node (ref "IC1") (pin "14") (pinfunction "OUT4_14") (pintype "output"))
    )
    (net (code "52") (name "Net-(IC1-SVR)") (class "Default")
      (node (ref "C35") (pin "+") (pinfunction "+_+") (pintype "passive"))
      (node (ref "IC1") (pin "6") (pinfunction "SVR_6") (pintype "passive"))
    )
    (net (code "53") (name "Net-(IC2-IN1)") (class "Default")
      (node (ref "C39") (pin "2") (pinfunction "2_2") (pintype "passive"))
      (node (ref "IC2") (pin "4") (pinfunction "IN1_4") (pintype "input"))
    )
    (net (code "54") (name "Net-(IC2-IN2)") (class "Default")
      (node (ref "C42") (pin "2") (pinfunction "2_2") (pintype "passive"))
      (node (ref "IC2") (pin "5") (pinfunction "IN2_5") (pintype "input"))
    )
    (net (code "55") (name "Net-(IC2-IN3)") (class "Default")
      (node (ref "C47") (pin "2") (pinfunction "2_2") (pintype "passive"))
      (node (ref "IC2") (pin "12") (pinfunction "IN3_12") (pintype "input"))
    )
    (net (code "56") (name "Net-(IC2-IN4)") (class "Default")
      (node (ref "C45") (pin "2") (pinfunction "2_2") (pintype "passive"))
      (node (ref "IC2") (pin "11") (pinfunction "IN4_11") (pintype "input"))
    )
    (net (code "57") (name "Net-(IC2-OUT1)") (class "Default")
      (node (ref "C40") (pin "+") (pinfunction "+_+") (pintype "passive"))
      (node (ref "IC2") (pin "1") (pinfunction "OUT1_1") (pintype "output"))
    )
    (net (code "58") (name "Net-(IC2-OUT2)") (class "Default")
      (node (ref "C41") (pin "+") (pinfunction "+_+") (pintype "passive"))
      (node (ref "IC2") (pin "2") (pinfunction "OUT2_2") (pintype "output"))
    )
    (net (code "59") (name "Net-(IC2-OUT3)") (class "Default")
      (node (ref "C44") (pin "+") (pinfunction "+_+") (pintype "passive"))
      (node (ref "IC2") (pin "15") (pinfunction "OUT3_15") (pintype "output"))
    )
    (net (code "60") (name "Net-(IC2-OUT4)") (class "Default")
      (node (ref "C43") (pin "+") (pinfunction "+_+") (pintype "passive"))
      (node (ref "IC2") (pin "14") (pinfunction "OUT4_14") (pintype "output"))
    )
    (net (code "61") (name "Net-(IC2-SVR)") (class "Default")
      (node (ref "C46") (pin "+") (pinfunction "+_+") (pintype "passive"))
      (node (ref "IC2") (pin "6") (pinfunction "SVR_6") (pintype "passive"))
    )
    (net (code "62") (name "Net-(JP3-Pad2)") (class "Default")
      (node (ref "JP3") (pin "2") (pinfunction "2_2") (pintype "passive"))
      (node (ref "R17") (pin "1") (pinfunction "1_1") (pintype "passive"))
    )
    (net (code "63") (name "Net-(LED1-PadA)") (class "Default")
      (node (ref "LED1") (pin "A") (pinfunction "A_A") (pintype "passive"))
      (node (ref "R18") (pin "1") (pinfunction "1_1") (pintype "passive"))
    )
    (net (code "64") (name "Net-(LED2-PadA)") (class "Default")
      (node (ref "LED2") (pin "A") (pinfunction "A_A") (pintype "passive"))
      (node (ref "R19") (pin "1") (pinfunction "1_1") (pintype "passive"))
    )
    (net (code "65") (name "Net-(LED3-PadA)") (class "Default")
      (node (ref "LED3") (pin "A") (pinfunction "A_A") (pintype "passive"))
      (node (ref "R21") (pin "1") (pinfunction "1_1") (pintype "passive"))
    )
    (net (code "66") (name "Net-(LED4-PadA)") (class "Default")
      (node (ref "LED4") (pin "A") (pinfunction "A_A") (pintype "passive"))
      (node (ref "R22") (pin "1") (pinfunction "1_1") (pintype "passive"))
    )
    (net (code "67") (name "Net-(R20-Pad1)") (class "Default")
      (node (ref "R20") (pin "1") (pinfunction "1_1") (pintype "passive"))
      (node (ref "S1") (pin "1") (pinfunction "1_1") (pintype "passive"))
    )
    (net (code "68") (name "Net-(X2A-KL)") (class "Default")
      (node (ref "C29") (pin "-") (pinfunction "-_-") (pintype "passive"))
      (node (ref "X2") (pin "1") (pinfunction "KL_1") (pintype "passive"))
    )
    (net (code "69") (name "Net-(X3A-KL)") (class "Default")
      (node (ref "C30") (pin "-") (pinfunction "-_-") (pintype "passive"))
      (node (ref "X3") (pin "1") (pinfunction "KL_1") (pintype "passive"))
    )
    (net (code "70") (name "Net-(X5A-KL)") (class "Default")
      (node (ref "C32") (pin "-") (pinfunction "-_-") (pintype "passive"))
      (node (ref "X5") (pin "1") (pinfunction "KL_1") (pintype "passive"))
    )
    (net (code "71") (name "Net-(X6A-KL)") (class "Default")
      (node (ref "C33") (pin "-") (pinfunction "-_-") (pintype "passive"))
      (node (ref "X6") (pin "1") (pinfunction "KL_1") (pintype "passive"))
    )
    (net (code "72") (name "Net-(X10A-KL)") (class "Default")
      (node (ref "C40") (pin "-") (pinfunction "-_-") (pintype "passive"))
      (node (ref "X10") (pin "1") (pinfunction "KL_1") (pintype "passive"))
    )
    (net (code "73") (name "Net-(X11A-KL)") (class "Default")
      (node (ref "C41") (pin "-") (pinfunction "-_-") (pintype "passive"))
      (node (ref "X11") (pin "1") (pinfunction "KL_1") (pintype "passive"))
    )
    (net (code "74") (name "Net-(X13A-KL)") (class "Default")
      (node (ref "C43") (pin "-") (pinfunction "-_-") (pintype "passive"))
      (node (ref "X13") (pin "1") (pinfunction "KL_1") (pintype "passive"))
    )
    (net (code "75") (name "Net-(X14A-KL)") (class "Default")
      (node (ref "C44") (pin "-") (pinfunction "-_-") (pintype "passive"))
      (node (ref "X14") (pin "1") (pinfunction "KL_1") (pintype "passive"))
    )
    (net (code "76") (name "Net-(X17B-KL)") (class "Default")
      (node (ref "D1") (pin "A") (pinfunction "A_A") (pintype "passive"))
      (node (ref "JP6") (pin "PWR") (pinfunction "PWR_PWR") (pintype "bidirectional"))
      (node (ref "X17") (pin "2") (pinfunction "KL_2") (pintype "passive"))
    )
    (net (code "77") (name "unconnected-(B1-0(RX0)-Pad0)") (class "Default")
      (node (ref "B1") (pin "0") (pinfunction "0(RX0)_0") (pintype "bidirectional"))
    )
    (net (code "78") (name "unconnected-(B1-1(TX0)-Pad1)") (class "Default")
      (node (ref "B1") (pin "1") (pinfunction "1(TX0)_1") (pintype "bidirectional"))
    )
    (net (code "79") (name "unconnected-(B1-5V-Pad5V@0)") (class "Default")
      (node (ref "B1") (pin "5V@0") (pinfunction "5V_5V@0") (pintype "bidirectional"))
    )
    (net (code "80") (name "unconnected-(B1-17(RX2)-Pad17)") (class "Default")
      (node (ref "B1") (pin "17") (pinfunction "17(RX2)_17") (pintype "bidirectional"))
    )
    (net (code "81") (name "unconnected-(B1-18(TX1)-Pad18)") (class "Default")
      (node (ref "B1") (pin "18") (pinfunction "18(TX1)_18") (pintype "bidirectional"))
    )
    (net (code "82") (name "unconnected-(B1-19(RX1)-Pad19)") (class "Default")
      (node (ref "B1") (pin "19") (pinfunction "19(RX1)_19") (pintype "bidirectional"))
    )
    (net (code "83") (name "unconnected-(B1-20(SDA)-Pad20)") (class "Default")
      (node (ref "B1") (pin "20") (pinfunction "20(SDA)_20") (pintype "bidirectional"))
    )
    (net (code "84") (name "unconnected-(B1-21(SCL)-Pad21)") (class "Default")
      (node (ref "B1") (pin "21") (pinfunction "21(SCL)_21") (pintype "bidirectional"))
    )
    (net (code "85") (name "unconnected-(B1-A0(RX0)-PadA0)") (class "Default")
      (node (ref "B1") (pin "A0") (pinfunction "A0(RX0)_A0") (pintype "bidirectional"))
    )
    (net (code "86") (name "unconnected-(B1-A1(TX0)-PadA1)") (class "Default")
      (node (ref "B1") (pin "A1") (pinfunction "A1(TX0)_A1") (pintype "bidirectional"))
    )
    (net (code "87") (name "unconnected-(B1-PadA2)") (class "Default")
      (node (ref "B1") (pin "A2") (pinfunction "A2_A2") (pintype "bidirectional"))
    )
    (net (code "88") (name "unconnected-(B1-PadA3)") (class "Default")
      (node (ref "B1") (pin "A3") (pinfunction "A3_A3") (pintype "bidirectional"))
    )
    (net (code "89") (name "unconnected-(B1-PadA4)") (class "Default")
      (node (ref "B1") (pin "A4") (pinfunction "A4_A4") (pintype "bidirectional"))
    )
    (net (code "90") (name "unconnected-(B1-PadA5)") (class "Default")
      (node (ref "B1") (pin "A5") (pinfunction "A5_A5") (pintype "bidirectional"))
    )
    (net (code "91") (name "unconnected-(B1-PadA6)") (class "Default")
      (node (ref "B1") (pin "A6") (pinfunction "A6_A6") (pintype "bidirectional"))
    )
    (net (code "92") (name "unconnected-(B1-PadA7)") (class "Default")
      (node (ref "B1") (pin "A7") (pinfunction "A7_A7") (pintype "bidirectional"))
    )
    (net (code "93") (name "unconnected-(B1-PadA8)") (class "Default")
      (node (ref "B1") (pin "A8") (pinfunction "A8_A8") (pintype "bidirectional"))
    )
    (net (code "94") (name "unconnected-(B1-PadA9)") (class "Default")
      (node (ref "B1") (pin "A9") (pinfunction "A9_A9") (pintype "bidirectional"))
    )
    (net (code "95") (name "unconnected-(B1-PadA10)") (class "Default")
      (node (ref "B1") (pin "A10") (pinfunction "A10_A10") (pintype "bidirectional"))
    )
    (net (code "96") (name "unconnected-(B1-PadA11)") (class "Default")
      (node (ref "B1") (pin "A11") (pinfunction "A11_A11") (pintype "bidirectional"))
    )
    (net (code "97") (name "unconnected-(B1-PadA12)") (class "Default")
      (node (ref "B1") (pin "A12") (pinfunction "A12_A12") (pintype "bidirectional"))
    )
    (net (code "98") (name "unconnected-(B1-PadA13)") (class "Default")
      (node (ref "B1") (pin "A13") (pinfunction "A13_A13") (pintype "bidirectional"))
    )
    (net (code "99") (name "unconnected-(B1-PadA14)") (class "Default")
      (node (ref "B1") (pin "A14") (pinfunction "A14_A14") (pintype "bidirectional"))
    )
    (net (code "100") (name "unconnected-(B1-PadA15)") (class "Default")
      (node (ref "B1") (pin "A15") (pinfunction "A15_A15") (pintype "bidirectional"))
    )
    (net (code "101") (name "unconnected-(B1-PadAREF)") (class "Default")
      (node (ref "B1") (pin "AREF") (pinfunction "AREF_AREF") (pintype "bidirectional"))
    )
    (net (code "102") (name "unconnected-(B1-PadRESET)") (class "Default")
      (node (ref "B1") (pin "RESET") (pinfunction "RESET_RESET") (pintype "bidirectional"))
    )
    (net (code "103") (name "unconnected-(IC1-DIAG-Pad10)") (class "Default")
      (node (ref "IC1") (pin "10") (pinfunction "DIAG_10") (pintype "passive"))
    )
    (net (code "104") (name "unconnected-(IC2-DIAG-Pad10)") (class "Default")
      (node (ref "IC2") (pin "10") (pinfunction "DIAG_10") (pintype "passive"))
    )
  )
)
